# Fan_and_Pump_Headers.net
KiCad netlist of a schematic drawn in Altium Designer
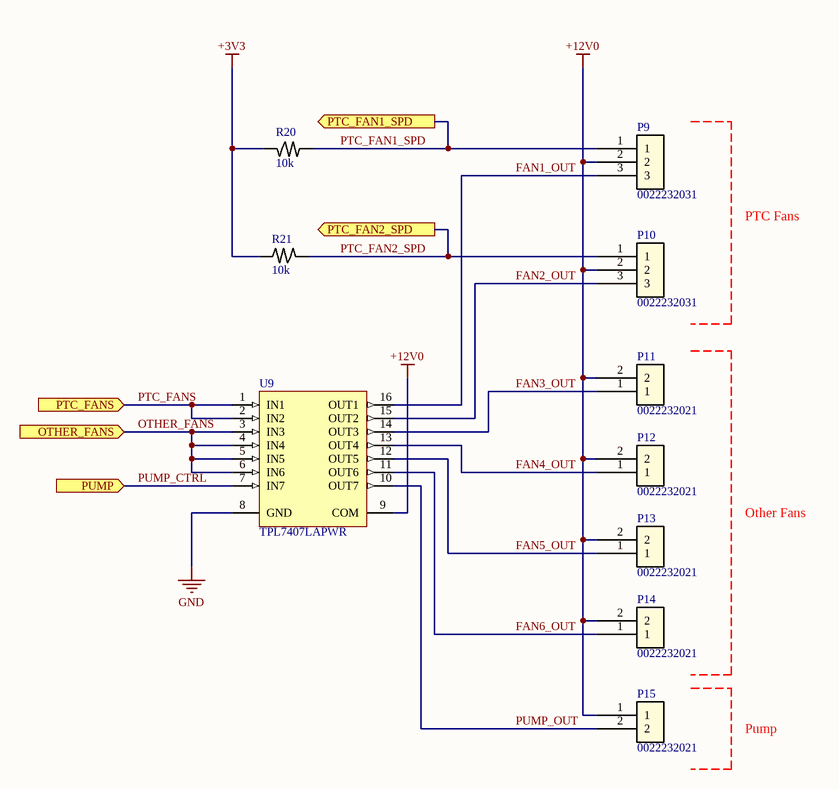
[diagram p0: Fan and Pump Headers.SchDoc]

(export (version "E")
  (design (tool "Eeschema 10.0.6"))
  (components
    (comp (ref "P9")
      (value "0022232031")
      (footprint "Signal3")
      (description "SignalConnector, 3 leads")
      (fields (field (name "MF") "Molex"))
      (libsource (lib "Connectors") (part "Signal3"))
    )
    (comp (ref "P10")
      (value "0022232031")
      (footprint "Signal3")
      (description "SignalConnector, 3 leads")
      (fields (field (name "MF") "Molex"))
      (libsource (lib "Connectors") (part "Signal3"))
    )
    (comp (ref "P11")
      (value "0022232021")
      (footprint "Signal2")
      (description "SignalConnector, 2 leads")
      (fields (field (name "MF") "Molex"))
      (libsource (lib "") (part "Signal2_1"))
    )
    (comp (ref "P12")
      (value "0022232021")
      (footprint "Signal2")
      (description "SignalConnector, 2 leads")
      (fields (field (name "MF") "Molex"))
      (libsource (lib "") (part "Signal2_1"))
    )
    (comp (ref "P13")
      (value "0022232021")
      (footprint "Signal2")
      (description "SignalConnector, 2 leads")
      (fields (field (name "MF") "Molex"))
      (libsource (lib "") (part "Signal2_1"))
    )
    (comp (ref "P14")
      (value "0022232021")
      (footprint "Signal2")
      (description "SignalConnector, 2 leads")
      (fields (field (name "MF") "Molex"))
      (libsource (lib "") (part "Signal2_1"))
    )
    (comp (ref "P15")
      (value "0022232021")
      (footprint "Signal2")
      (description "SignalConnector, 2 leads")
      (fields (field (name "MF") "Molex"))
      (libsource (lib "Connectors") (part "Signal2"))
    )
    (comp (ref "R20")
      (value "10k")
      (footprint "R0603")
      (description "RES 10kΩ ±1% 100mW 0603")
      (fields (field (name "MF") "FOJAN") (field (name "MP") "FRC0603F1002TS"))
      (libsource (lib "Components") (part "Res"))
    )
    (comp (ref "R21")
      (value "10k")
      (footprint "R0603")
      (description "RES 10kΩ ±1% 100mW 0603")
      (fields (field (name "MF") "FOJAN") (field (name "MP") "FRC0603F1002TS"))
      (libsource (lib "Components") (part "Res"))
    )
    (comp (ref "U9")
      (value "TPL7407LAPWR")
      (footprint "TSSOP-16")
      (description "7 Active High Low Side Switch TSSOP-16 Power Distribution Switches, Load Drivers ROHS")
      (fields (field (name "MF") "Texas Instruments"))
      (libsource (lib "Components") (part "TPL7407LAPWR FET Array"))
    )
  )
  (nets
    (net (code "1") (name "+3V3") (class "Default")
      (node (ref "R20") (pin "2") (pinfunction "2_2") (pintype "passive"))
      (node (ref "R21") (pin "1") (pinfunction "1_1") (pintype "passive"))
    )
    (net (code "2") (name "+12V0") (class "Default")
      (node (ref "P10") (pin "2") (pinfunction "2_2") (pintype "passive"))
      (node (ref "P11") (pin "2") (pinfunction "2_2") (pintype "passive"))
      (node (ref "P12") (pin "2") (pinfunction "2_2") (pintype "passive"))
      (node (ref "P13") (pin "2") (pinfunction "2_2") (pintype "passive"))
      (node (ref "P14") (pin "2") (pinfunction "2_2") (pintype "passive"))
      (node (ref "P15") (pin "1") (pinfunction "1_1") (pintype "passive"))
      (node (ref "P9") (pin "2") (pinfunction "2_2") (pintype "passive"))
      (node (ref "U9") (pin "9") (pinfunction "COM_9") (pintype "power_in"))
    )
    (net (code "3") (name "/FAN1_OUT") (class "Default")
      (node (ref "P9") (pin "3") (pinfunction "3_3") (pintype "passive"))
      (node (ref "U9") (pin "16") (pinfunction "OUT1_16") (pintype "output"))
    )
    (net (code "4") (name "/FAN2_OUT") (class "Default")
      (node (ref "P10") (pin "3") (pinfunction "3_3") (pintype "passive"))
      (node (ref "U9") (pin "15") (pinfunction "OUT2_15") (pintype "output"))
    )
    (net (code "5") (name "/FAN3_OUT") (class "Default")
      (node (ref "P11") (pin "1") (pinfunction "1_1") (pintype "passive"))
      (node (ref "U9") (pin "14") (pinfunction "OUT3_14") (pintype "output"))
    )
    (net (code "6") (name "/FAN4_OUT") (class "Default")
      (node (ref "P12") (pin "1") (pinfunction "1_1") (pintype "passive"))
      (node (ref "U9") (pin "13") (pinfunction "OUT4_13") (pintype "output"))
    )
    (net (code "7") (name "/FAN5_OUT") (class "Default")
      (node (ref "P13") (pin "1") (pinfunction "1_1") (pintype "passive"))
      (node (ref "U9") (pin "12") (pinfunction "OUT5_12") (pintype "output"))
    )
    (net (code "8") (name "/FAN6_OUT") (class "Default")
      (node (ref "P14") (pin "1") (pinfunction "1_1") (pintype "passive"))
      (node (ref "U9") (pin "11") (pinfunction "OUT6_11") (pintype "output"))
    )
    (net (code "9") (name "/OTHER_FANS") (class "Default")
      (node (ref "U9") (pin "3") (pinfunction "IN3_3") (pintype "input"))
      (node (ref "U9") (pin "4") (pinfunction "IN4_4") (pintype "input"))
      (node (ref "U9") (pin "5") (pinfunction "IN5_5") (pintype "input"))
      (node (ref "U9") (pin "6") (pinfunction "IN6_6") (pintype "input"))
    )
    (net (code "10") (name "/PTC_FAN1_SPD") (class "Default")
      (node (ref "P9") (pin "1") (pinfunction "1_1") (pintype "passive"))
      (node (ref "R20") (pin "1") (pinfunction "1_1") (pintype "passive"))
    )
    (net (code "11") (name "/PTC_FAN2_SPD") (class "Default")
      (node (ref "P10") (pin "1") (pinfunction "1_1") (pintype "passive"))
      (node (ref "R21") (pin "2") (pinfunction "2_2") (pintype "passive"))
    )
    (net (code "12") (name "/PTC_FANS") (class "Default")
      (node (ref "U9") (pin "1") (pinfunction "IN1_1") (pintype "input"))
      (node (ref "U9") (pin "2") (pinfunction "IN2_2") (pintype "input"))
    )
    (net (code "13") (name "/PUMP_CTRL") (class "Default")
      (node (ref "U9") (pin "7") (pinfunction "IN7_7") (pintype "input"))
    )
    (net (code "14") (name "/PUMP_OUT") (class "Default")
      (node (ref "P15") (pin "2") (pinfunction "2_2") (pintype "passive"))
      (node (ref "U9") (pin "10") (pinfunction "OUT7_10") (pintype "output"))
    )
    (net (code "15") (name "GND") (class "Default")
      (node (ref "U9") (pin "8") (pinfunction "GND_8") (pintype "power_in"))
    )
  )
)
